# mix_bpf.net
KiCad netlist of a schematic drawn in Altium Designer
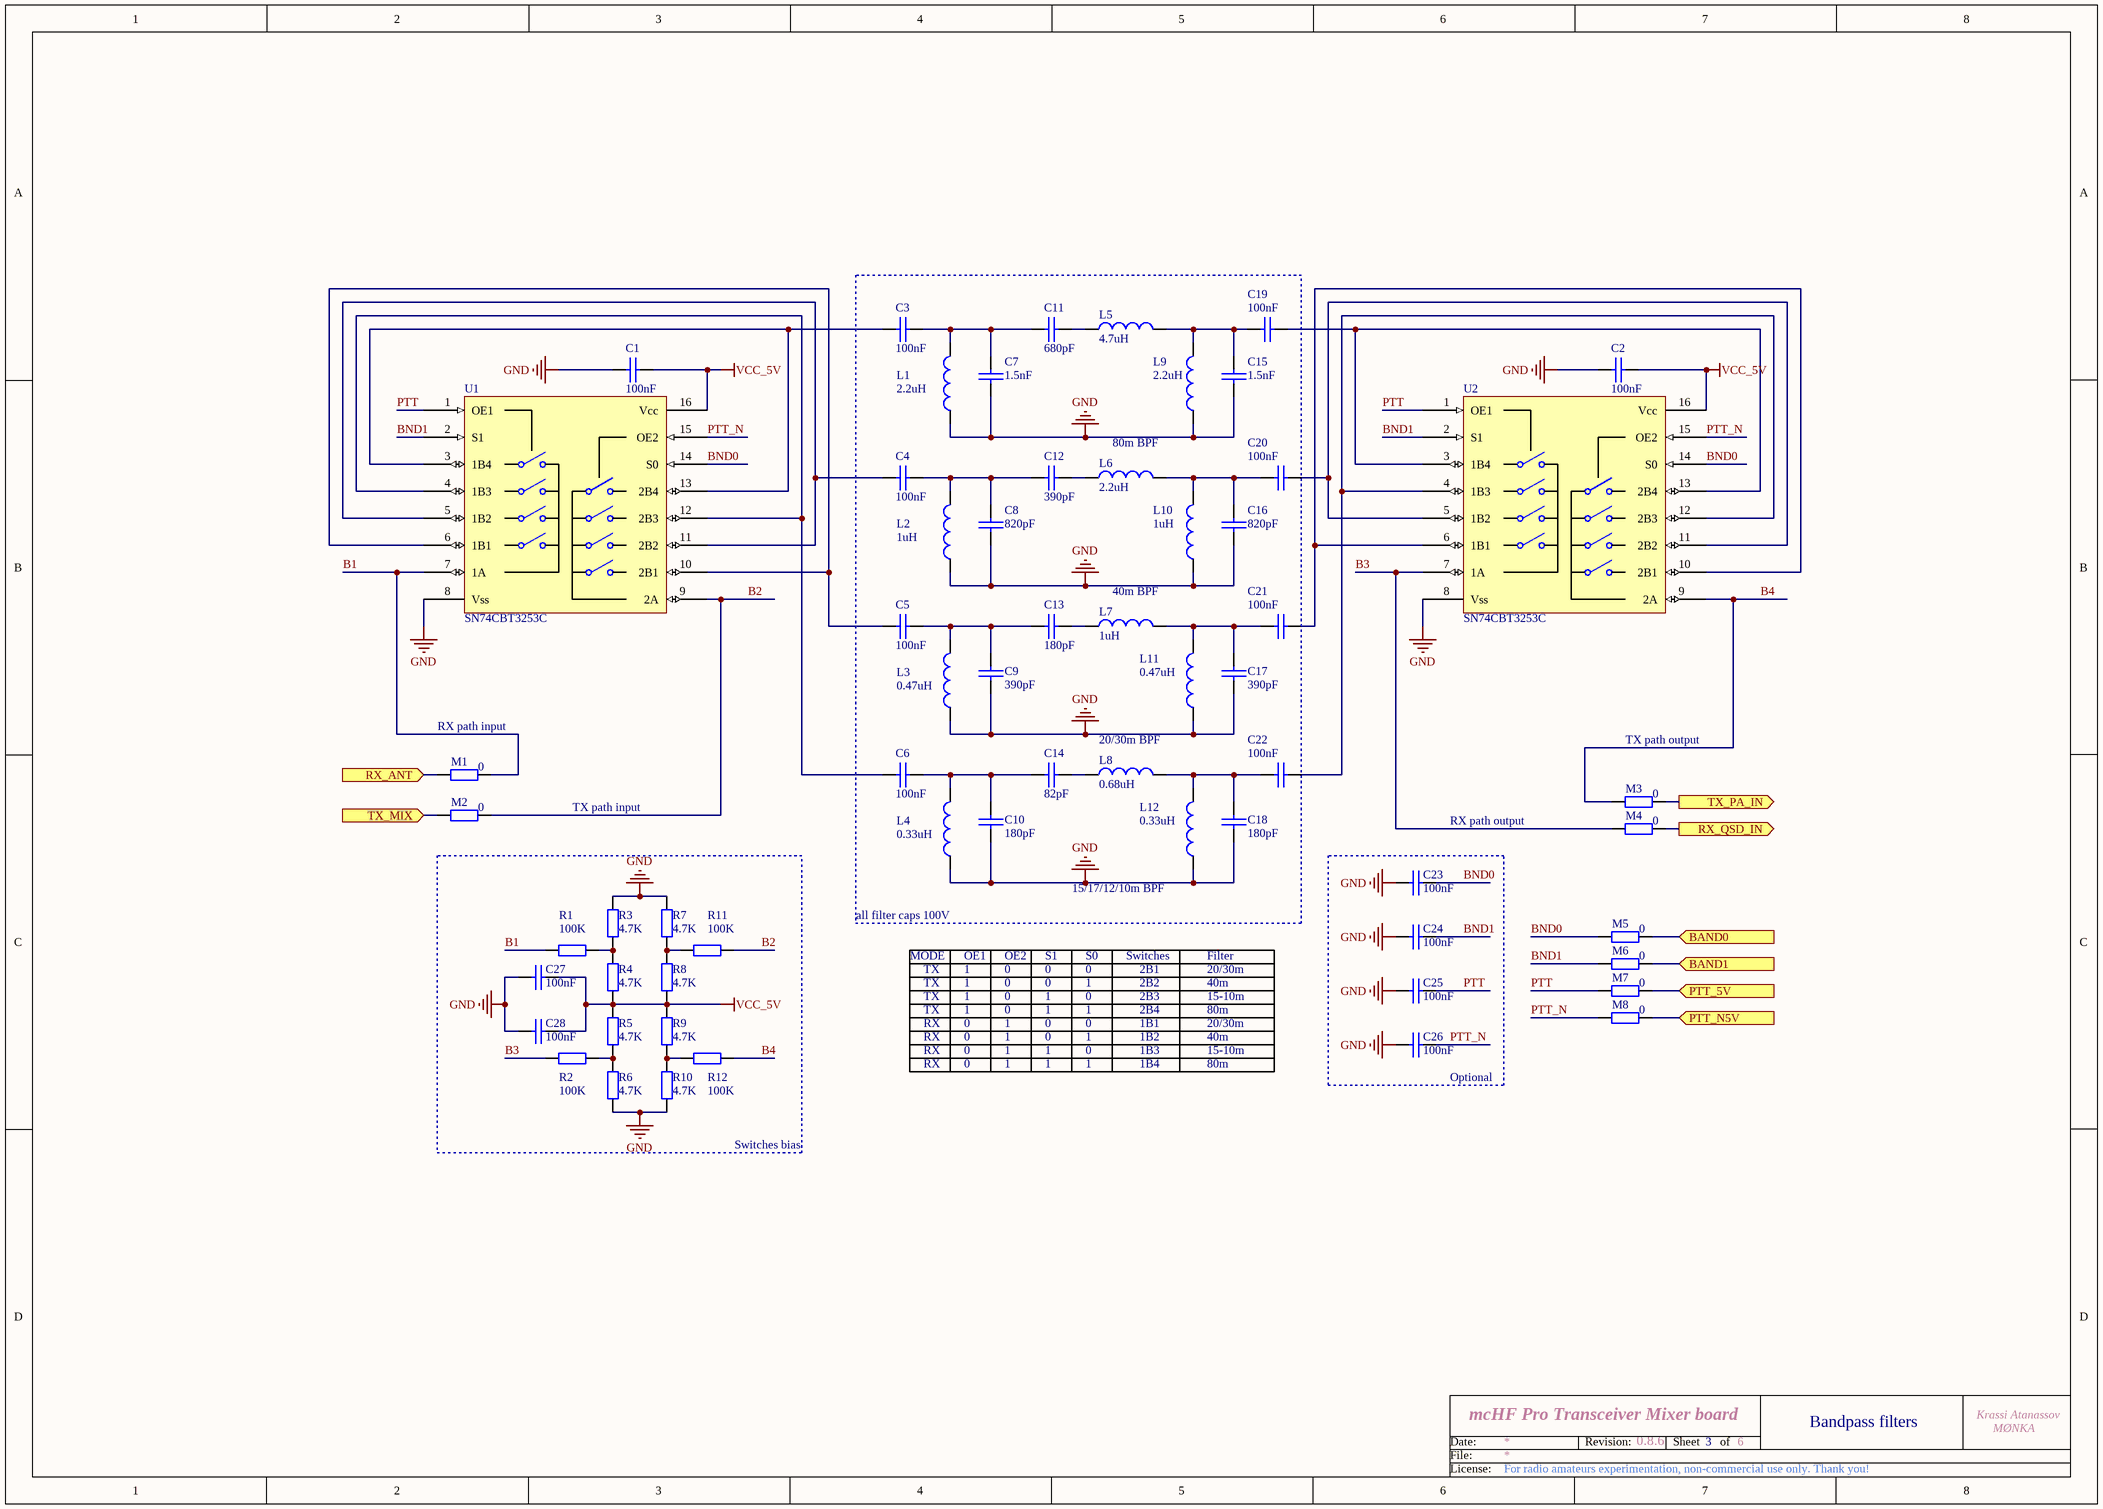
[diagram p0: mix_bpf.SchDoc]

(export (version "E")
  (design (tool "Eeschema 10.0.6"))
  (components
    (comp (ref "C1")
      (value "100nF")
      (footprint "0805")
      (description "Capacitor")
      (libsource (lib "mcHF_rf") (part "CAP"))
    )
    (comp (ref "C2")
      (value "100nF")
      (footprint "0805")
      (description "Capacitor")
      (libsource (lib "mcHF_rf") (part "CAP"))
    )
    (comp (ref "C3")
      (value "100nF")
      (footprint "0805")
      (description "Capacitor")
      (libsource (lib "mcHF_rf") (part "CAP"))
    )
    (comp (ref "C4")
      (value "100nF")
      (footprint "0805")
      (description "Capacitor")
      (libsource (lib "mcHF_rf") (part "CAP"))
    )
    (comp (ref "C5")
      (value "100nF")
      (footprint "0805")
      (description "Capacitor")
      (libsource (lib "mcHF_rf") (part "CAP"))
    )
    (comp (ref "C6")
      (value "100nF")
      (footprint "0805")
      (description "Capacitor")
      (libsource (lib "mcHF_rf") (part "CAP"))
    )
    (comp (ref "C7")
      (value "1.5nF")
      (footprint "0805")
      (description "Capacitor")
      (libsource (lib "mcHF_rf") (part "CAP"))
    )
    (comp (ref "C8")
      (value "820pF")
      (footprint "0805")
      (description "Capacitor")
      (libsource (lib "mcHF_rf") (part "CAP"))
    )
    (comp (ref "C9")
      (value "390pF")
      (footprint "0805")
      (description "Capacitor")
      (libsource (lib "mcHF_rf") (part "CAP"))
    )
    (comp (ref "C10")
      (value "180pF")
      (footprint "0805")
      (description "Capacitor")
      (libsource (lib "mcHF_rf") (part "CAP"))
    )
    (comp (ref "C11")
      (value "680pF")
      (footprint "0805")
      (description "Capacitor")
      (libsource (lib "mcHF_rf") (part "CAP"))
    )
    (comp (ref "C12")
      (value "390pF")
      (footprint "0805")
      (description "Capacitor")
      (libsource (lib "mcHF_rf") (part "CAP"))
    )
    (comp (ref "C13")
      (value "180pF")
      (footprint "0805")
      (description "Capacitor")
      (libsource (lib "mcHF_rf") (part "CAP"))
    )
    (comp (ref "C14")
      (value "82pF")
      (footprint "0805")
      (description "Capacitor")
      (libsource (lib "mcHF_rf") (part "CAP"))
    )
    (comp (ref "C15")
      (value "1.5nF")
      (footprint "0805")
      (description "Capacitor")
      (libsource (lib "mcHF_rf") (part "CAP"))
    )
    (comp (ref "C16")
      (value "820pF")
      (footprint "0805")
      (description "Capacitor")
      (libsource (lib "mcHF_rf") (part "CAP"))
    )
    (comp (ref "C17")
      (value "390pF")
      (footprint "0805")
      (description "Capacitor")
      (libsource (lib "mcHF_rf") (part "CAP"))
    )
    (comp (ref "C18")
      (value "180pF")
      (footprint "0805")
      (description "Capacitor")
      (libsource (lib "mcHF_rf") (part "CAP"))
    )
    (comp (ref "C19")
      (value "100nF")
      (footprint "0805")
      (description "Capacitor")
      (libsource (lib "mcHF_rf") (part "CAP"))
    )
    (comp (ref "C20")
      (value "100nF")
      (footprint "0805")
      (description "Capacitor")
      (libsource (lib "mcHF_rf") (part "CAP"))
    )
    (comp (ref "C21")
      (value "100nF")
      (footprint "0805")
      (description "Capacitor")
      (libsource (lib "mcHF_rf") (part "CAP"))
    )
    (comp (ref "C22")
      (value "100nF")
      (footprint "0805")
      (description "Capacitor")
      (libsource (lib "mcHF_rf") (part "CAP"))
    )
    (comp (ref "C23")
      (value "100nF")
      (footprint "0805")
      (description "Capacitor")
      (libsource (lib "mcHF_rf") (part "CAP"))
    )
    (comp (ref "C24")
      (value "100nF")
      (footprint "0805")
      (description "Capacitor")
      (libsource (lib "mcHF_rf") (part "CAP"))
    )
    (comp (ref "C25")
      (value "100nF")
      (footprint "0805")
      (description "Capacitor")
      (libsource (lib "mcHF_rf") (part "CAP"))
    )
    (comp (ref "C26")
      (value "100nF")
      (footprint "0805")
      (description "Capacitor")
      (libsource (lib "mcHF_rf") (part "CAP"))
    )
    (comp (ref "C27")
      (value "100nF")
      (footprint "0805")
      (description "Capacitor")
      (libsource (lib "mcHF_rf") (part "CAP"))
    )
    (comp (ref "C28")
      (value "100nF")
      (footprint "0805")
      (description "Capacitor")
      (libsource (lib "mcHF_rf") (part "CAP"))
    )
    (comp (ref "L1")
      (value "2.2uH")
      (footprint "0805")
      (description "INDUCTOR SMD")
      (libsource (lib "mcHF_rf") (part "BPF_IND"))
    )
    (comp (ref "L2")
      (value "1uH")
      (footprint "0805")
      (description "INDUCTOR SMD")
      (libsource (lib "mcHF_rf") (part "BPF_IND"))
    )
    (comp (ref "L3")
      (value "0.47uH")
      (footprint "0805")
      (description "INDUCTOR SMD")
      (libsource (lib "mcHF_rf") (part "BPF_IND"))
    )
    (comp (ref "L4")
      (value "0.33uH")
      (footprint "0805")
      (description "INDUCTOR SMD")
      (libsource (lib "mcHF_rf") (part "BPF_IND"))
    )
    (comp (ref "L5")
      (value "4.7uH")
      (footprint "0805")
      (description "INDUCTOR SMD")
      (libsource (lib "mcHF_rf") (part "BPF_IND"))
    )
    (comp (ref "L6")
      (value "2.2uH")
      (footprint "0805")
      (description "INDUCTOR SMD")
      (libsource (lib "mcHF_rf") (part "BPF_IND"))
    )
    (comp (ref "L7")
      (value "1uH")
      (footprint "0805")
      (description "INDUCTOR SMD")
      (libsource (lib "mcHF_rf") (part "BPF_IND"))
    )
    (comp (ref "L8")
      (value "0.68uH")
      (footprint "0805")
      (description "INDUCTOR SMD")
      (libsource (lib "mcHF_rf") (part "BPF_IND"))
    )
    (comp (ref "L9")
      (value "2.2uH")
      (footprint "0805")
      (description "INDUCTOR SMD")
      (libsource (lib "mcHF_rf") (part "BPF_IND"))
    )
    (comp (ref "L10")
      (value "1uH")
      (footprint "0805")
      (description "INDUCTOR SMD")
      (libsource (lib "mcHF_rf") (part "BPF_IND"))
    )
    (comp (ref "L11")
      (value "0.47uH")
      (footprint "0805")
      (description "INDUCTOR SMD")
      (libsource (lib "mcHF_rf") (part "BPF_IND"))
    )
    (comp (ref "L12")
      (value "0.33uH")
      (footprint "0805")
      (description "INDUCTOR SMD")
      (libsource (lib "mcHF_rf") (part "BPF_IND"))
    )
    (comp (ref "M1")
      (value "0")
      (footprint "0805")
      (description "Resistor")
      (libsource (lib "mcHF_rf") (part "RES"))
    )
    (comp (ref "M2")
      (value "0")
      (footprint "0805")
      (description "Resistor")
      (libsource (lib "mcHF_rf") (part "RES"))
    )
    (comp (ref "M3")
      (value "0")
      (footprint "0805")
      (description "Resistor")
      (libsource (lib "mcHF_rf") (part "RES"))
    )
    (comp (ref "M4")
      (value "0")
      (footprint "0805")
      (description "Resistor")
      (libsource (lib "mcHF_rf") (part "RES"))
    )
    (comp (ref "M5")
      (value "0")
      (footprint "0805")
      (description "Resistor")
      (libsource (lib "mcHF_rf") (part "RES"))
    )
    (comp (ref "M6")
      (value "0")
      (footprint "0805")
      (description "Resistor")
      (libsource (lib "mcHF_rf") (part "RES"))
    )
    (comp (ref "M7")
      (value "0")
      (footprint "0805")
      (description "Resistor")
      (libsource (lib "mcHF_rf") (part "RES"))
    )
    (comp (ref "M8")
      (value "0")
      (footprint "0805")
      (description "Resistor")
      (libsource (lib "mcHF_rf") (part "RES"))
    )
    (comp (ref "R1")
      (value "100K")
      (footprint "0805")
      (description "Resistor")
      (libsource (lib "") (part "RES_2"))
    )
    (comp (ref "R2")
      (value "100K")
      (footprint "0805")
      (description "Resistor")
      (libsource (lib "") (part "RES_2"))
    )
    (comp (ref "R3")
      (value "4.7K")
      (footprint "0805")
      (description "Resistor")
      (libsource (lib "") (part "RES_1"))
    )
    (comp (ref "R4")
      (value "4.7K")
      (footprint "0805")
      (description "Resistor")
      (libsource (lib "") (part "RES_1"))
    )
    (comp (ref "R5")
      (value "4.7K")
      (footprint "0805")
      (description "Resistor")
      (libsource (lib "") (part "RES_1"))
    )
    (comp (ref "R6")
      (value "4.7K")
      (footprint "0805")
      (description "Resistor")
      (libsource (lib "") (part "RES_1"))
    )
    (comp (ref "R7")
      (value "4.7K")
      (footprint "0805")
      (description "Resistor")
      (libsource (lib "") (part "RES_1"))
    )
    (comp (ref "R8")
      (value "4.7K")
      (footprint "0805")
      (description "Resistor")
      (libsource (lib "") (part "RES_1"))
    )
    (comp (ref "R9")
      (value "4.7K")
      (footprint "0805")
      (description "Resistor")
      (libsource (lib "") (part "RES_1"))
    )
    (comp (ref "R10")
      (value "4.7K")
      (footprint "0805")
      (description "Resistor")
      (libsource (lib "") (part "RES_1"))
    )
    (comp (ref "R11")
      (value "100K")
      (footprint "0805")
      (description "Resistor")
      (libsource (lib "") (part "RES_2"))
    )
    (comp (ref "R12")
      (value "100K")
      (footprint "0805")
      (description "Resistor")
      (libsource (lib "") (part "RES_2"))
    )
    (comp (ref "U1")
      (value "SN74CBT3253C")
      (footprint "SO-16")
      (description "Dual 4:1 Demux/Analog Switch")
      (libsource (lib "mcHF_rf") (part "SN74CBT3253C"))
    )
    (comp (ref "U2")
      (value "SN74CBT3253C")
      (footprint "SO-16")
      (description "Dual 4:1 Demux/Analog Switch")
      (libsource (lib "mcHF_rf") (part "SN74CBT3253C"))
    )
  )
  (nets
    (net (code "1") (name "/B1") (class "Default")
      (node (ref "M1") (pin "1") (pinfunction "1_1") (pintype "passive"))
      (node (ref "R1") (pin "1") (pinfunction "1_1") (pintype "passive"))
      (node (ref "U1") (pin "7") (pinfunction "1A_7") (pintype "bidirectional"))
    )
    (net (code "2") (name "/B2") (class "Default")
      (node (ref "M2") (pin "1") (pinfunction "1_1") (pintype "passive"))
      (node (ref "R11") (pin "2") (pinfunction "2_2") (pintype "passive"))
      (node (ref "U1") (pin "9") (pinfunction "2A_9") (pintype "bidirectional"))
    )
    (net (code "3") (name "/B3") (class "Default")
      (node (ref "M4") (pin "2") (pinfunction "2_2") (pintype "passive"))
      (node (ref "R2") (pin "1") (pinfunction "1_1") (pintype "passive"))
      (node (ref "U2") (pin "7") (pinfunction "1A_7") (pintype "bidirectional"))
    )
    (net (code "4") (name "/B4") (class "Default")
      (node (ref "M3") (pin "2") (pinfunction "2_2") (pintype "passive"))
      (node (ref "R12") (pin "2") (pinfunction "2_2") (pintype "passive"))
      (node (ref "U2") (pin "9") (pinfunction "2A_9") (pintype "bidirectional"))
    )
    (net (code "5") (name "/BAND0") (class "Default")
      (node (ref "M5") (pin "1") (pinfunction "1_1") (pintype "passive"))
    )
    (net (code "6") (name "/BAND1") (class "Default")
      (node (ref "M6") (pin "1") (pinfunction "1_1") (pintype "passive"))
    )
    (net (code "7") (name "/BND0") (class "Default")
      (node (ref "C23") (pin "1") (pinfunction "1_1") (pintype "passive"))
      (node (ref "M5") (pin "2") (pinfunction "2_2") (pintype "passive"))
      (node (ref "U1") (pin "14") (pinfunction "S0_14") (pintype "input"))
      (node (ref "U2") (pin "14") (pinfunction "S0_14") (pintype "input"))
    )
    (net (code "8") (name "/BND1") (class "Default")
      (node (ref "C24") (pin "1") (pinfunction "1_1") (pintype "passive"))
      (node (ref "M6") (pin "2") (pinfunction "2_2") (pintype "passive"))
      (node (ref "U1") (pin "2") (pinfunction "S1_2") (pintype "input"))
      (node (ref "U2") (pin "2") (pinfunction "S1_2") (pintype "input"))
    )
    (net (code "9") (name "/PTT") (class "Default")
      (node (ref "C25") (pin "1") (pinfunction "1_1") (pintype "passive"))
      (node (ref "M7") (pin "2") (pinfunction "2_2") (pintype "passive"))
      (node (ref "U1") (pin "1") (pinfunction "OE1_1") (pintype "input"))
      (node (ref "U2") (pin "1") (pinfunction "OE1_1") (pintype "input"))
    )
    (net (code "10") (name "/PTT_5V") (class "Default")
      (node (ref "M7") (pin "1") (pinfunction "1_1") (pintype "passive"))
    )
    (net (code "11") (name "/PTT_N") (class "Default")
      (node (ref "C26") (pin "1") (pinfunction "1_1") (pintype "passive"))
      (node (ref "M8") (pin "2") (pinfunction "2_2") (pintype "passive"))
      (node (ref "U1") (pin "15") (pinfunction "OE2_15") (pintype "input"))
      (node (ref "U2") (pin "15") (pinfunction "OE2_15") (pintype "input"))
    )
    (net (code "12") (name "/PTT_N5V") (class "Default")
      (node (ref "M8") (pin "1") (pinfunction "1_1") (pintype "passive"))
    )
    (net (code "13") (name "/RX_ANT") (class "Default")
      (node (ref "M1") (pin "2") (pinfunction "2_2") (pintype "passive"))
    )
    (net (code "14") (name "/RX_QSD_IN") (class "Default")
      (node (ref "M4") (pin "1") (pinfunction "1_1") (pintype "passive"))
    )
    (net (code "15") (name "/TX_MIX") (class "Default")
      (node (ref "M2") (pin "2") (pinfunction "2_2") (pintype "passive"))
    )
    (net (code "16") (name "/TX_PA_IN") (class "Default")
      (node (ref "M3") (pin "1") (pinfunction "1_1") (pintype "passive"))
    )
    (net (code "17") (name "GND") (class "Default")
      (node (ref "C1") (pin "2") (pinfunction "2_2") (pintype "passive"))
      (node (ref "C10") (pin "1") (pinfunction "1_1") (pintype "passive"))
      (node (ref "C15") (pin "2") (pinfunction "2_2") (pintype "passive"))
      (node (ref "C16") (pin "2") (pinfunction "2_2") (pintype "passive"))
      (node (ref "C17") (pin "1") (pinfunction "1_1") (pintype "passive"))
      (node (ref "C18") (pin "1") (pinfunction "1_1") (pintype "passive"))
      (node (ref "C2") (pin "2") (pinfunction "2_2") (pintype "passive"))
      (node (ref "C23") (pin "2") (pinfunction "2_2") (pintype "passive"))
      (node (ref "C24") (pin "2") (pinfunction "2_2") (pintype "passive"))
      (node (ref "C25") (pin "2") (pinfunction "2_2") (pintype "passive"))
      (node (ref "C26") (pin "2") (pinfunction "2_2") (pintype "passive"))
      (node (ref "C27") (pin "2") (pinfunction "2_2") (pintype "passive"))
      (node (ref "C28") (pin "2") (pinfunction "2_2") (pintype "passive"))
      (node (ref "C7") (pin "2") (pinfunction "2_2") (pintype "passive"))
      (node (ref "C8") (pin "2") (pinfunction "2_2") (pintype "passive"))
      (node (ref "C9") (pin "1") (pinfunction "1_1") (pintype "passive"))
      (node (ref "L1") (pin "1") (pinfunction "1_1") (pintype "passive"))
      (node (ref "L10") (pin "1") (pinfunction "1_1") (pintype "passive"))
      (node (ref "L11") (pin "1") (pinfunction "1_1") (pintype "passive"))
      (node (ref "L12") (pin "1") (pinfunction "1_1") (pintype "passive"))
      (node (ref "L2") (pin "1") (pinfunction "1_1") (pintype "passive"))
      (node (ref "L3") (pin "1") (pinfunction "1_1") (pintype "passive"))
      (node (ref "L4") (pin "1") (pinfunction "1_1") (pintype "passive"))
      (node (ref "L9") (pin "1") (pinfunction "1_1") (pintype "passive"))
      (node (ref "R10") (pin "2") (pinfunction "2_2") (pintype "passive"))
      (node (ref "R3") (pin "1") (pinfunction "1_1") (pintype "passive"))
      (node (ref "R6") (pin "2") (pinfunction "2_2") (pintype "passive"))
      (node (ref "R7") (pin "1") (pinfunction "1_1") (pintype "passive"))
      (node (ref "U1") (pin "8") (pinfunction "Vss_8") (pintype "power_in"))
      (node (ref "U2") (pin "8") (pinfunction "Vss_8") (pintype "power_in"))
    )
    (net (code "18") (name "Net-(C10-Pad2)") (class "Default")
      (node (ref "C10") (pin "2") (pinfunction "2_2") (pintype "passive"))
      (node (ref "C14") (pin "1") (pinfunction "1_1") (pintype "passive"))
      (node (ref "C6") (pin "1") (pinfunction "1_1") (pintype "passive"))
      (node (ref "L4") (pin "2") (pinfunction "2_2") (pintype "passive"))
    )
    (net (code "19") (name "Net-(C11-Pad1)") (class "Default")
      (node (ref "C11") (pin "1") (pinfunction "1_1") (pintype "passive"))
      (node (ref "C3") (pin "1") (pinfunction "1_1") (pintype "passive"))
      (node (ref "C7") (pin "1") (pinfunction "1_1") (pintype "passive"))
      (node (ref "L1") (pin "2") (pinfunction "2_2") (pintype "passive"))
    )
    (net (code "20") (name "Net-(C11-Pad2)") (class "Default")
      (node (ref "C11") (pin "2") (pinfunction "2_2") (pintype "passive"))
      (node (ref "L5") (pin "1") (pinfunction "1_1") (pintype "passive"))
    )
    (net (code "21") (name "Net-(C12-Pad1)") (class "Default")
      (node (ref "C12") (pin "1") (pinfunction "1_1") (pintype "passive"))
      (node (ref "C4") (pin "1") (pinfunction "1_1") (pintype "passive"))
      (node (ref "C8") (pin "1") (pinfunction "1_1") (pintype "passive"))
      (node (ref "L2") (pin "2") (pinfunction "2_2") (pintype "passive"))
    )
    (net (code "22") (name "Net-(C12-Pad2)") (class "Default")
      (node (ref "C12") (pin "2") (pinfunction "2_2") (pintype "passive"))
      (node (ref "L6") (pin "1") (pinfunction "1_1") (pintype "passive"))
    )
    (net (code "23") (name "Net-(C13-Pad1)") (class "Default")
      (node (ref "C13") (pin "1") (pinfunction "1_1") (pintype "passive"))
      (node (ref "C5") (pin "1") (pinfunction "1_1") (pintype "passive"))
      (node (ref "C9") (pin "2") (pinfunction "2_2") (pintype "passive"))
      (node (ref "L3") (pin "2") (pinfunction "2_2") (pintype "passive"))
    )
    (net (code "24") (name "Net-(C13-Pad2)") (class "Default")
      (node (ref "C13") (pin "2") (pinfunction "2_2") (pintype "passive"))
      (node (ref "L7") (pin "1") (pinfunction "1_1") (pintype "passive"))
    )
    (net (code "25") (name "Net-(C14-Pad2)") (class "Default")
      (node (ref "C14") (pin "2") (pinfunction "2_2") (pintype "passive"))
      (node (ref "L8") (pin "1") (pinfunction "1_1") (pintype "passive"))
    )
    (net (code "26") (name "Net-(C15-Pad1)") (class "Default")
      (node (ref "C15") (pin "1") (pinfunction "1_1") (pintype "passive"))
      (node (ref "C19") (pin "2") (pinfunction "2_2") (pintype "passive"))
      (node (ref "L5") (pin "2") (pinfunction "2_2") (pintype "passive"))
      (node (ref "L9") (pin "2") (pinfunction "2_2") (pintype "passive"))
    )
    (net (code "27") (name "Net-(C16-Pad1)") (class "Default")
      (node (ref "C16") (pin "1") (pinfunction "1_1") (pintype "passive"))
      (node (ref "C20") (pin "2") (pinfunction "2_2") (pintype "passive"))
      (node (ref "L10") (pin "2") (pinfunction "2_2") (pintype "passive"))
      (node (ref "L6") (pin "2") (pinfunction "2_2") (pintype "passive"))
    )
    (net (code "28") (name "Net-(C17-Pad2)") (class "Default")
      (node (ref "C17") (pin "2") (pinfunction "2_2") (pintype "passive"))
      (node (ref "C21") (pin "2") (pinfunction "2_2") (pintype "passive"))
      (node (ref "L11") (pin "2") (pinfunction "2_2") (pintype "passive"))
      (node (ref "L7") (pin "2") (pinfunction "2_2") (pintype "passive"))
    )
    (net (code "29") (name "Net-(C18-Pad2)") (class "Default")
      (node (ref "C18") (pin "2") (pinfunction "2_2") (pintype "passive"))
      (node (ref "C22") (pin "2") (pinfunction "2_2") (pintype "passive"))
      (node (ref "L12") (pin "2") (pinfunction "2_2") (pintype "passive"))
      (node (ref "L8") (pin "2") (pinfunction "2_2") (pintype "passive"))
    )
    (net (code "30") (name "Net-(R1-Pad2)") (class "Default")
      (node (ref "R1") (pin "2") (pinfunction "2_2") (pintype "passive"))
      (node (ref "R3") (pin "2") (pinfunction "2_2") (pintype "passive"))
      (node (ref "R4") (pin "1") (pinfunction "1_1") (pintype "passive"))
    )
    (net (code "31") (name "Net-(R2-Pad2)") (class "Default")
      (node (ref "R2") (pin "2") (pinfunction "2_2") (pintype "passive"))
      (node (ref "R5") (pin "2") (pinfunction "2_2") (pintype "passive"))
      (node (ref "R6") (pin "1") (pinfunction "1_1") (pintype "passive"))
    )
    (net (code "32") (name "Net-(R10-Pad1)") (class "Default")
      (node (ref "R10") (pin "1") (pinfunction "1_1") (pintype "passive"))
      (node (ref "R12") (pin "1") (pinfunction "1_1") (pintype "passive"))
      (node (ref "R9") (pin "2") (pinfunction "2_2") (pintype "passive"))
    )
    (net (code "33") (name "Net-(R11-Pad1)") (class "Default")
      (node (ref "R11") (pin "1") (pinfunction "1_1") (pintype "passive"))
      (node (ref "R7") (pin "2") (pinfunction "2_2") (pintype "passive"))
      (node (ref "R8") (pin "1") (pinfunction "1_1") (pintype "passive"))
    )
    (net (code "34") (name "Net-(U1-1B1)") (class "Default")
      (node (ref "C5") (pin "2") (pinfunction "2_2") (pintype "passive"))
      (node (ref "U1") (pin "10") (pinfunction "2B1_10") (pintype "bidirectional"))
      (node (ref "U1") (pin "6") (pinfunction "1B1_6") (pintype "bidirectional"))
    )
    (net (code "35") (name "Net-(U1-1B2)") (class "Default")
      (node (ref "C4") (pin "2") (pinfunction "2_2") (pintype "passive"))
      (node (ref "U1") (pin "11") (pinfunction "2B2_11") (pintype "bidirectional"))
      (node (ref "U1") (pin "5") (pinfunction "1B2_5") (pintype "bidirectional"))
    )
    (net (code "36") (name "Net-(U1-1B3)") (class "Default")
      (node (ref "C6") (pin "2") (pinfunction "2_2") (pintype "passive"))
      (node (ref "U1") (pin "12") (pinfunction "2B3_12") (pintype "bidirectional"))
      (node (ref "U1") (pin "4") (pinfunction "1B3_4") (pintype "bidirectional"))
    )
    (net (code "37") (name "Net-(U1-1B4)") (class "Default")
      (node (ref "C3") (pin "2") (pinfunction "2_2") (pintype "passive"))
      (node (ref "U1") (pin "13") (pinfunction "2B4_13") (pintype "bidirectional"))
      (node (ref "U1") (pin "3") (pinfunction "1B4_3") (pintype "bidirectional"))
    )
    (net (code "38") (name "Net-(U2-1B1)") (class "Default")
      (node (ref "C21") (pin "1") (pinfunction "1_1") (pintype "passive"))
      (node (ref "U2") (pin "10") (pinfunction "2B1_10") (pintype "bidirectional"))
      (node (ref "U2") (pin "6") (pinfunction "1B1_6") (pintype "bidirectional"))
    )
    (net (code "39") (name "Net-(U2-1B2)") (class "Default")
      (node (ref "C20") (pin "1") (pinfunction "1_1") (pintype "passive"))
      (node (ref "U2") (pin "11") (pinfunction "2B2_11") (pintype "bidirectional"))
      (node (ref "U2") (pin "5") (pinfunction "1B2_5") (pintype "bidirectional"))
    )
    (net (code "40") (name "Net-(U2-1B3)") (class "Default")
      (node (ref "C22") (pin "1") (pinfunction "1_1") (pintype "passive"))
      (node (ref "U2") (pin "12") (pinfunction "2B3_12") (pintype "bidirectional"))
      (node (ref "U2") (pin "4") (pinfunction "1B3_4") (pintype "bidirectional"))
    )
    (net (code "41") (name "Net-(U2-1B4)") (class "Default")
      (node (ref "C19") (pin "1") (pinfunction "1_1") (pintype "passive"))
      (node (ref "U2") (pin "13") (pinfunction "2B4_13") (pintype "bidirectional"))
      (node (ref "U2") (pin "3") (pinfunction "1B4_3") (pintype "bidirectional"))
    )
    (net (code "42") (name "VCC_5V") (class "Default")
      (node (ref "C1") (pin "1") (pinfunction "1_1") (pintype "passive"))
      (node (ref "C2") (pin "1") (pinfunction "1_1") (pintype "passive"))
      (node (ref "C27") (pin "1") (pinfunction "1_1") (pintype "passive"))
      (node (ref "C28") (pin "1") (pinfunction "1_1") (pintype "passive"))
      (node (ref "R4") (pin "2") (pinfunction "2_2") (pintype "passive"))
      (node (ref "R5") (pin "1") (pinfunction "1_1") (pintype "passive"))
      (node (ref "R8") (pin "2") (pinfunction "2_2") (pintype "passive"))
      (node (ref "R9") (pin "1") (pinfunction "1_1") (pintype "passive"))
      (node (ref "U1") (pin "16") (pinfunction "Vcc_16") (pintype "power_in"))
      (node (ref "U2") (pin "16") (pinfunction "Vcc_16") (pintype "power_in"))
    )
  )
)
